# 2226051___ATmega128_Sheet.net
KiCad netlist of a schematic drawn in Altium Designer
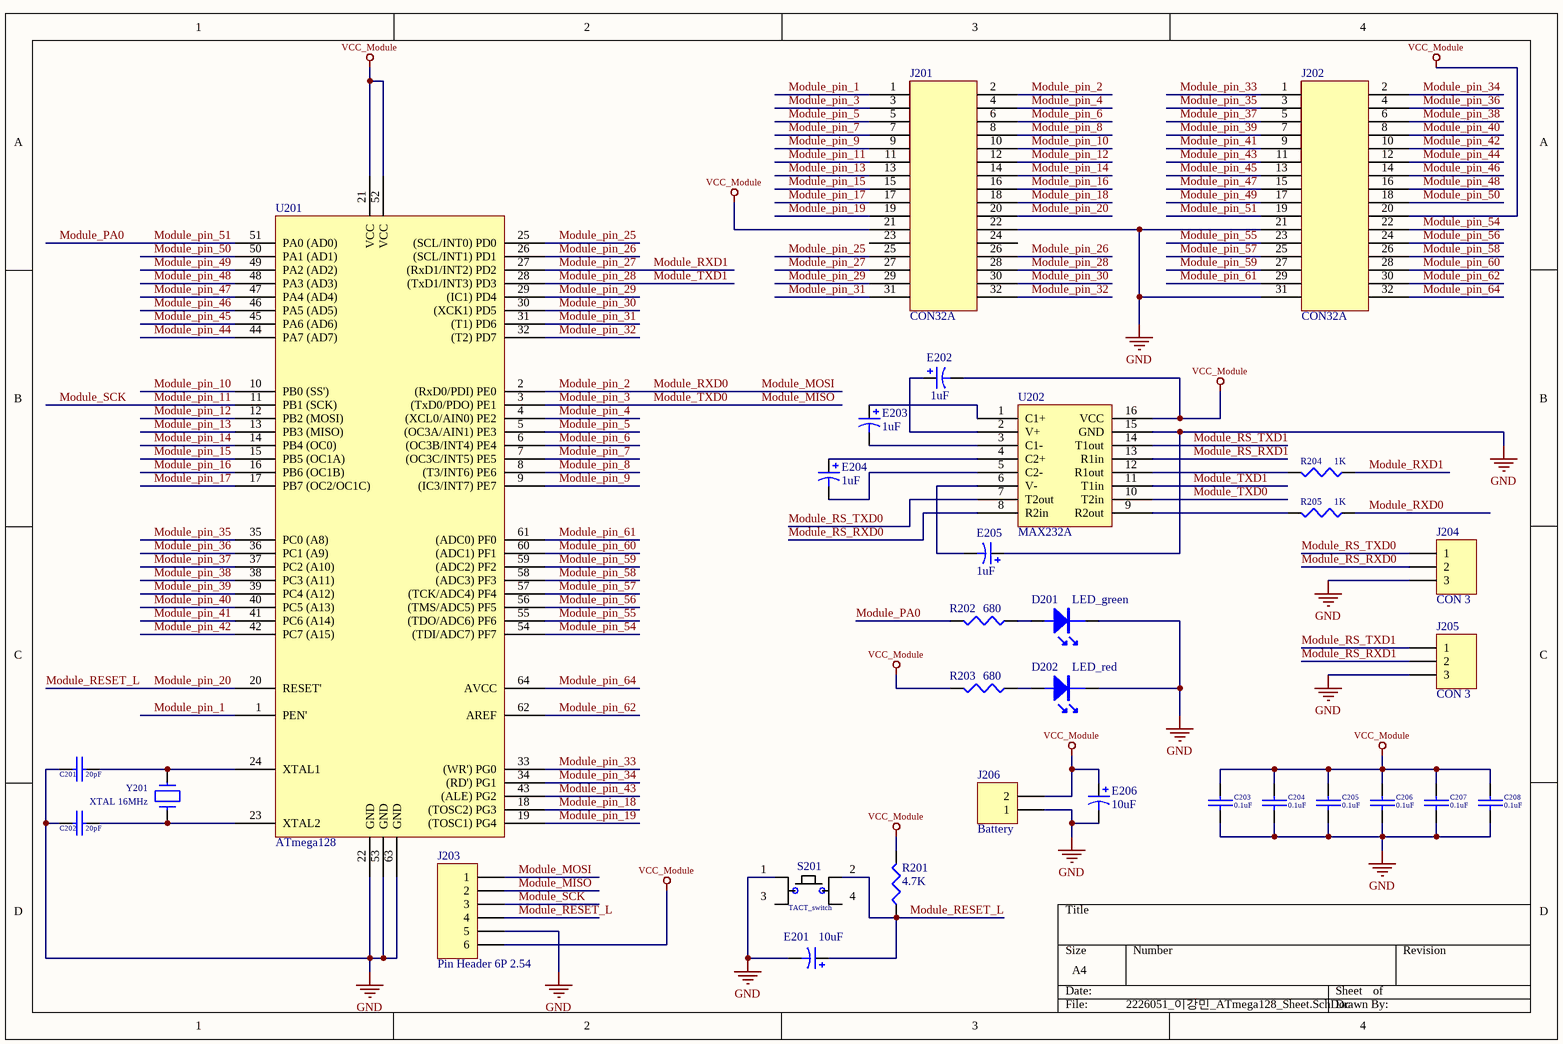
[diagram p0: 2226051_이강민_ATmega128_Sheet.SchDoc]

(export (version "E")
  (design (tool "Eeschema 10.0.6"))
  (components
    (comp (ref "C201")
      (value "20pF")
      (footprint "0603C1608")
      (description "SMDCapacitor")
      (libsource (lib "Miscellaneous Devices-KST") (part "CAP-Chip"))
    )
    (comp (ref "C202")
      (value "20pF")
      (footprint "0603C1608")
      (description "SMDCapacitor")
      (libsource (lib "Miscellaneous Devices-KST") (part "CAP-Chip"))
    )
    (comp (ref "C203")
      (value "0.1uF")
      (footprint "0603C1608")
      (description "SMDCapacitor")
      (libsource (lib "Miscellaneous Devices-KST") (part "CAP-Chip"))
    )
    (comp (ref "C204")
      (value "0.1uF")
      (footprint "0603C1608")
      (description "SMDCapacitor")
      (libsource (lib "Miscellaneous Devices-KST") (part "CAP-Chip"))
    )
    (comp (ref "C205")
      (value "0.1uF")
      (footprint "0603C1608")
      (description "SMDCapacitor")
      (libsource (lib "Miscellaneous Devices-KST") (part "CAP-Chip"))
    )
    (comp (ref "C206")
      (value "0.1uF")
      (footprint "0603C1608")
      (description "SMDCapacitor")
      (libsource (lib "Miscellaneous Devices-KST") (part "CAP-Chip"))
    )
    (comp (ref "C207")
      (value "0.1uF")
      (footprint "0603C1608")
      (description "SMDCapacitor")
      (libsource (lib "Miscellaneous Devices-KST") (part "CAP-Chip"))
    )
    (comp (ref "C208")
      (value "0.1uF")
      (footprint "0603C1608")
      (description "SMDCapacitor")
      (libsource (lib "Miscellaneous Devices-KST") (part "CAP-Chip"))
    )
    (comp (ref "D201")
      (value "LED_green")
      (footprint "LED-2012")
      (libsource (lib "Miscellaneous Devices-KST") (part "LED"))
    )
    (comp (ref "D202")
      (value "LED_red")
      (footprint "LED-2012")
      (libsource (lib "Miscellaneous Devices-KST") (part "LED"))
    )
    (comp (ref "E201")
      (value "10uF")
      (footprint "C0805")
      (description "Polarized Capacitor (Surface Mount)")
      (fields (field (name "Comment") "Cap Pol3") (field (name "PUBLISHER") "Altium Limited"))
      (libsource (lib "Miscellaneous Devices") (part "Cap Pol3"))
    )
    (comp (ref "E202")
      (value "1uF")
      (footprint "C0805")
      (description "Polarized Capacitor (Surface Mount)")
      (fields (field (name "Comment") "Cap Pol3") (field (name "PUBLISHER") "Altium Limited"))
      (libsource (lib "Miscellaneous Devices") (part "Cap Pol3"))
    )
    (comp (ref "E203")
      (value "1uF")
      (footprint "C0805")
      (description "Polarized Capacitor (Surface Mount)")
      (fields (field (name "Comment") "Cap Pol3") (field (name "PUBLISHER") "Altium Limited"))
      (libsource (lib "Miscellaneous Devices") (part "Cap Pol3"))
    )
    (comp (ref "E204")
      (value "1uF")
      (footprint "C0805")
      (description "Polarized Capacitor (Surface Mount)")
      (fields (field (name "Comment") "Cap Pol3") (field (name "PUBLISHER") "Altium Limited"))
      (libsource (lib "Miscellaneous Devices") (part "Cap Pol3"))
    )
    (comp (ref "E205")
      (value "1uF")
      (footprint "C0805")
      (description "Polarized Capacitor (Surface Mount)")
      (fields (field (name "Comment") "Cap Pol3") (field (name "PUBLISHER") "Altium Limited"))
      (libsource (lib "Miscellaneous Devices") (part "Cap Pol3"))
    )
    (comp (ref "E206")
      (value "10uF")
      (footprint "C0805")
      (description "Polarized Capacitor (Surface Mount)")
      (fields (field (name "Comment") "Cap Pol3") (field (name "PUBLISHER") "Altium Limited"))
      (libsource (lib "Miscellaneous Devices") (part "Cap Pol3"))
    )
    (comp (ref "J201")
      (value "CON32A")
      (footprint "CON32A")
      (libsource (lib "2226051_이강민_Schlib1") (part "CON32A"))
    )
    (comp (ref "J202")
      (value "CON32A")
      (footprint "CON32A")
      (libsource (lib "2226051_이강민_Schlib1") (part "CON32A"))
    )
    (comp (ref "J203")
      (value "Pin Header 6P 2.54")
      (footprint "ISP_connector")
      (description "Header, 6-Pin")
      (fields (field (name "PUBLISHER") "Altium Limited"))
      (libsource (lib "Miscellaneous Connectors") (part "Header 6"))
    )
    (comp (ref "J204")
      (value "CON 3")
      (footprint "RS-232_connector")
      (description "Header, 3-Pin")
      (fields (field (name "PUBLISHER") "Altium Limited"))
      (libsource (lib "Miscellaneous Connectors") (part "Header 3"))
    )
    (comp (ref "J205")
      (value "CON 3")
      (footprint "RS-232_connector")
      (description "Header, 3-Pin")
      (fields (field (name "PUBLISHER") "Altium Limited"))
      (libsource (lib "Miscellaneous Connectors") (part "Header 3"))
    )
    (comp (ref "J206")
      (value "Battery")
      (footprint "battery_2pin")
      (description "Header, 2-Pin")
      (fields (field (name "PUBLISHER") "Altium Limited"))
      (libsource (lib "Miscellaneous Connectors") (part "Header 2"))
    )
    (comp (ref "R201")
      (value "4.7K")
      (footprint "J1-0603")
      (description "Resistor")
      (fields (field (name "Comment") "Res3") (field (name "PUBLISHER") "Altium Limited"))
      (libsource (lib "Miscellaneous Devices") (part "Res3"))
    )
    (comp (ref "R202")
      (value "680")
      (footprint "J1-0603")
      (description "Resistor")
      (fields (field (name "Comment") "Res3") (field (name "PUBLISHER") "Altium Limited"))
      (libsource (lib "Miscellaneous Devices") (part "Res3"))
    )
    (comp (ref "R203")
      (value "680")
      (footprint "J1-0603")
      (description "Resistor")
      (fields (field (name "Comment") "Res3") (field (name "PUBLISHER") "Altium Limited"))
      (libsource (lib "Miscellaneous Devices") (part "Res3"))
    )
    (comp (ref "R204")
      (value "1K")
      (footprint "J1-0603")
      (description "Resistor")
      (fields (field (name "Comment") "Res3") (field (name "PUBLISHER") "Altium Limited"))
      (libsource (lib "Miscellaneous Devices") (part "Res3"))
    )
    (comp (ref "R205")
      (value "1K")
      (footprint "J1-0603")
      (description "Resistor")
      (fields (field (name "Comment") "Res3") (field (name "PUBLISHER") "Altium Limited"))
      (libsource (lib "Miscellaneous Devices") (part "Res3"))
    )
    (comp (ref "S201")
      (value "TACT_switch")
      (footprint "IT-1109S")
      (libsource (lib "2226051_이강민_Schlib1") (part "TACT_switch"))
    )
    (comp (ref "U201")
      (value "ATmega128")
      (footprint "ATmega128_1414")
      (libsource (lib "2226051_이강민_Schlib1") (part "ATmega128"))
    )
    (comp (ref "U202")
      (value "MAX232A")
      (footprint "MAX232A")
      (libsource (lib "2226051_이강민_Schlib1") (part "MAX232A"))
    )
    (comp (ref "Y201")
      (value "XTAL 16MHz")
      (footprint "X-TAL_SMD")
      (description "Crystal")
      (libsource (lib "Miscellaneous Devices-KST") (part "CRYSTAL"))
    )
  )
  (nets
    (net (code "1") (name "/Module_MISO") (class "Default")
      (node (ref "J201") (pin "3") (pintype "passive"))
      (node (ref "J203") (pin "2") (pinfunction "2_2") (pintype "passive"))
      (node (ref "U201") (pin "3") (pinfunction "(TxD0/PDO)_PE1_3") (pintype "passive"))
      (node (ref "U202") (pin "10") (pinfunction "T2in_10") (pintype "passive"))
    )
    (net (code "2") (name "/Module_MOSI") (class "Default")
      (node (ref "J201") (pin "2") (pintype "passive"))
      (node (ref "J203") (pin "1") (pinfunction "1_1") (pintype "passive"))
      (node (ref "R205") (pin "1") (pinfunction "1_1") (pintype "passive"))
      (node (ref "U201") (pin "2") (pinfunction "(RxD0/PDI)_PE0_2") (pintype "passive"))
    )
    (net (code "3") (name "/Module_PA0") (class "Default")
      (node (ref "J202") (pin "19") (pintype "passive"))
      (node (ref "R202") (pin "2") (pinfunction "2_2") (pintype "passive"))
      (node (ref "U201") (pin "51") (pinfunction "PA0_(AD0)_51") (pintype "passive"))
    )
    (net (code "4") (name "/Module_RESET_L") (class "Default")
      (node (ref "E201") (pin "1") (pinfunction "1_1") (pintype "passive"))
      (node (ref "J201") (pin "20") (pintype "passive"))
      (node (ref "J203") (pin "4") (pinfunction "4_4") (pintype "passive"))
      (node (ref "R201") (pin "1") (pinfunction "1_1") (pintype "passive"))
      (node (ref "S201") (pin "2") (pinfunction "2_2") (pintype "passive"))
      (node (ref "U201") (pin "20") (pinfunction "RESET'_20") (pintype "passive"))
    )
    (net (code "5") (name "/Module_RS_RXD0") (class "Default")
      (node (ref "J204") (pin "2") (pinfunction "2_2") (pintype "passive"))
      (node (ref "U202") (pin "8") (pinfunction "R2in_8") (pintype "passive"))
    )
    (net (code "6") (name "/Module_RS_RXD1") (class "Default")
      (node (ref "J205") (pin "2") (pinfunction "2_2") (pintype "passive"))
      (node (ref "U202") (pin "13") (pinfunction "R1in_13") (pintype "passive"))
    )
    (net (code "7") (name "/Module_RS_TXD0") (class "Default")
      (node (ref "J204") (pin "1") (pinfunction "1_1") (pintype "passive"))
      (node (ref "U202") (pin "7") (pinfunction "T2out_7") (pintype "passive"))
    )
    (net (code "8") (name "/Module_RS_TXD1") (class "Default")
      (node (ref "J205") (pin "1") (pinfunction "1_1") (pintype "passive"))
      (node (ref "U202") (pin "14") (pinfunction "T1out_14") (pintype "passive"))
    )
    (net (code "9") (name "/Module_RXD1") (class "Default")
      (node (ref "J201") (pin "27") (pintype "passive"))
      (node (ref "R204") (pin "1") (pinfunction "1_1") (pintype "passive"))
      (node (ref "U201") (pin "27") (pinfunction "(RxD1/INT2)_PD2_27") (pintype "passive"))
    )
    (net (code "10") (name "/Module_SCK") (class "Default")
      (node (ref "J201") (pin "11") (pintype "passive"))
      (node (ref "J203") (pin "3") (pinfunction "3_3") (pintype "passive"))
      (node (ref "U201") (pin "11") (pinfunction "PB1_(SCK)_11") (pintype "passive"))
    )
    (net (code "11") (name "/Module_TXD1") (class "Default")
      (node (ref "J201") (pin "28") (pintype "passive"))
      (node (ref "U201") (pin "28") (pinfunction "(TxD1/INT3)_PD3_28") (pintype "passive"))
      (node (ref "U202") (pin "11") (pinfunction "T1in_11") (pintype "passive"))
    )
    (net (code "12") (name "/Module_pin_1") (class "Default")
      (node (ref "J201") (pin "1") (pintype "passive"))
      (node (ref "U201") (pin "1") (pinfunction "PEN'_1") (pintype "passive"))
    )
    (net (code "13") (name "/Module_pin_4") (class "Default")
      (node (ref "J201") (pin "4") (pintype "passive"))
      (node (ref "U201") (pin "4") (pinfunction "(XCL0/AIN0)_PE2_4") (pintype "passive"))
    )
    (net (code "14") (name "/Module_pin_5") (class "Default")
      (node (ref "J201") (pin "5") (pintype "passive"))
      (node (ref "U201") (pin "5") (pinfunction "(OC3A/AIN1)_PE3_5") (pintype "passive"))
    )
    (net (code "15") (name "/Module_pin_6") (class "Default")
      (node (ref "J201") (pin "6") (pintype "passive"))
      (node (ref "U201") (pin "6") (pinfunction "(OC3B/INT4)_PE4_6") (pintype "passive"))
    )
    (net (code "16") (name "/Module_pin_7") (class "Default")
      (node (ref "J201") (pin "7") (pintype "passive"))
      (node (ref "U201") (pin "7") (pinfunction "(OC3C/INT5)_PE5_7") (pintype "passive"))
    )
    (net (code "17") (name "/Module_pin_8") (class "Default")
      (node (ref "J201") (pin "8") (pintype "passive"))
      (node (ref "U201") (pin "8") (pinfunction "(T3/INT6)_PE6_8") (pintype "passive"))
    )
    (net (code "18") (name "/Module_pin_9") (class "Default")
      (node (ref "J201") (pin "9") (pintype "passive"))
      (node (ref "U201") (pin "9") (pinfunction "(IC3/INT7)_PE7_9") (pintype "passive"))
    )
    (net (code "19") (name "/Module_pin_10") (class "Default")
      (node (ref "J201") (pin "10") (pintype "passive"))
      (node (ref "U201") (pin "10") (pinfunction "PB0_(SS')_10") (pintype "passive"))
    )
    (net (code "20") (name "/Module_pin_12") (class "Default")
      (node (ref "J201") (pin "12") (pintype "passive"))
      (node (ref "U201") (pin "12") (pinfunction "PB2_(MOSI)_12") (pintype "passive"))
    )
    (net (code "21") (name "/Module_pin_13") (class "Default")
      (node (ref "J201") (pin "13") (pintype "passive"))
      (node (ref "U201") (pin "13") (pinfunction "PB3_(MISO)_13") (pintype "passive"))
    )
    (net (code "22") (name "/Module_pin_14") (class "Default")
      (node (ref "J201") (pin "14") (pintype "passive"))
      (node (ref "U201") (pin "14") (pinfunction "PB4_(OC0)_14") (pintype "passive"))
    )
    (net (code "23") (name "/Module_pin_15") (class "Default")
      (node (ref "J201") (pin "15") (pintype "passive"))
      (node (ref "U201") (pin "15") (pinfunction "PB5_(OC1A)_15") (pintype "passive"))
    )
    (net (code "24") (name "/Module_pin_16") (class "Default")
      (node (ref "J201") (pin "16") (pintype "passive"))
      (node (ref "U201") (pin "16") (pinfunction "PB6_(OC1B)_16") (pintype "passive"))
    )
    (net (code "25") (name "/Module_pin_17") (class "Default")
      (node (ref "J201") (pin "17") (pintype "passive"))
      (node (ref "U201") (pin "17") (pinfunction "PB7_(OC2/OC1C)_17") (pintype "passive"))
    )
    (net (code "26") (name "/Module_pin_18") (class "Default")
      (node (ref "J201") (pin "18") (pintype "passive"))
      (node (ref "U201") (pin "18") (pinfunction "(TOSC2)_PG3_18") (pintype "passive"))
    )
    (net (code "27") (name "/Module_pin_19") (class "Default")
      (node (ref "J201") (pin "19") (pintype "passive"))
      (node (ref "U201") (pin "19") (pinfunction "(TOSC1)_PG4_19") (pintype "passive"))
    )
    (net (code "28") (name "/Module_pin_25") (class "Default")
      (node (ref "J201") (pin "25") (pintype "passive"))
      (node (ref "U201") (pin "25") (pinfunction "(SCL/INT0)_PD0_25") (pintype "passive"))
    )
    (net (code "29") (name "/Module_pin_26") (class "Default")
      (node (ref "J201") (pin "26") (pintype "passive"))
      (node (ref "U201") (pin "26") (pinfunction "(SCL/INT1)_PD1_26") (pintype "passive"))
    )
    (net (code "30") (name "/Module_pin_29") (class "Default")
      (node (ref "J201") (pin "29") (pintype "passive"))
      (node (ref "U201") (pin "29") (pinfunction "(IC1)_PD4_29") (pintype "passive"))
    )
    (net (code "31") (name "/Module_pin_30") (class "Default")
      (node (ref "J201") (pin "30") (pintype "passive"))
      (node (ref "U201") (pin "30") (pinfunction "(XCK1)_PD5_30") (pintype "passive"))
    )
    (net (code "32") (name "/Module_pin_31") (class "Default")
      (node (ref "J201") (pin "31") (pintype "passive"))
      (node (ref "U201") (pin "31") (pinfunction "(T1)_PD6_31") (pintype "passive"))
    )
    (net (code "33") (name "/Module_pin_32") (class "Default")
      (node (ref "J201") (pin "32") (pintype "passive"))
      (node (ref "U201") (pin "32") (pinfunction "(T2)_PD7_32") (pintype "passive"))
    )
    (net (code "34") (name "/Module_pin_33") (class "Default")
      (node (ref "J202") (pin "1") (pintype "passive"))
      (node (ref "U201") (pin "33") (pinfunction "(WR')_PG0_33") (pintype "passive"))
    )
    (net (code "35") (name "/Module_pin_34") (class "Default")
      (node (ref "J202") (pin "2") (pintype "passive"))
      (node (ref "U201") (pin "34") (pinfunction "(RD')_PG1_34") (pintype "passive"))
    )
    (net (code "36") (name "/Module_pin_35") (class "Default")
      (node (ref "J202") (pin "3") (pintype "passive"))
      (node (ref "U201") (pin "35") (pinfunction "PC0_(A8)_35") (pintype "passive"))
    )
    (net (code "37") (name "/Module_pin_36") (class "Default")
      (node (ref "J202") (pin "4") (pintype "passive"))
      (node (ref "U201") (pin "36") (pinfunction "PC1_(A9)_36") (pintype "passive"))
    )
    (net (code "38") (name "/Module_pin_37") (class "Default")
      (node (ref "J202") (pin "5") (pintype "passive"))
      (node (ref "U201") (pin "37") (pinfunction "PC2_(A10)_37") (pintype "passive"))
    )
    (net (code "39") (name "/Module_pin_38") (class "Default")
      (node (ref "J202") (pin "6") (pintype "passive"))
      (node (ref "U201") (pin "38") (pinfunction "PC3_(A11)_38") (pintype "passive"))
    )
    (net (code "40") (name "/Module_pin_39") (class "Default")
      (node (ref "J202") (pin "7") (pintype "passive"))
      (node (ref "U201") (pin "39") (pinfunction "PC4_(A12)_39") (pintype "passive"))
    )
    (net (code "41") (name "/Module_pin_40") (class "Default")
      (node (ref "J202") (pin "8") (pintype "passive"))
      (node (ref "U201") (pin "40") (pinfunction "PC5_(A13)_40") (pintype "passive"))
    )
    (net (code "42") (name "/Module_pin_41") (class "Default")
      (node (ref "J202") (pin "9") (pintype "passive"))
      (node (ref "U201") (pin "41") (pinfunction "PC6_(A14)_41") (pintype "passive"))
    )
    (net (code "43") (name "/Module_pin_42") (class "Default")
      (node (ref "J202") (pin "10") (pintype "passive"))
      (node (ref "U201") (pin "42") (pinfunction "PC7_(A15)_42") (pintype "passive"))
    )
    (net (code "44") (name "/Module_pin_43") (class "Default")
      (node (ref "J202") (pin "11") (pintype "passive"))
      (node (ref "U201") (pin "43") (pinfunction "(ALE)_PG2_43") (pintype "passive"))
    )
    (net (code "45") (name "/Module_pin_44") (class "Default")
      (node (ref "J202") (pin "12") (pintype "passive"))
      (node (ref "U201") (pin "44") (pinfunction "PA7_(AD7)_44") (pintype "passive"))
    )
    (net (code "46") (name "/Module_pin_45") (class "Default")
      (node (ref "J202") (pin "13") (pintype "passive"))
      (node (ref "U201") (pin "45") (pinfunction "PA6_(AD6)_45") (pintype "passive"))
    )
    (net (code "47") (name "/Module_pin_46") (class "Default")
      (node (ref "J202") (pin "14") (pintype "passive"))
      (node (ref "U201") (pin "46") (pinfunction "PA5_(AD5)_46") (pintype "passive"))
    )
    (net (code "48") (name "/Module_pin_47") (class "Default")
      (node (ref "J202") (pin "15") (pintype "passive"))
      (node (ref "U201") (pin "47") (pinfunction "PA4_(AD4)_47") (pintype "passive"))
    )
    (net (code "49") (name "/Module_pin_48") (class "Default")
      (node (ref "J202") (pin "16") (pintype "passive"))
      (node (ref "U201") (pin "48") (pinfunction "PA3_(AD3)_48") (pintype "passive"))
    )
    (net (code "50") (name "/Module_pin_49") (class "Default")
      (node (ref "J202") (pin "17") (pintype "passive"))
      (node (ref "U201") (pin "49") (pinfunction "PA2_(AD2)_49") (pintype "passive"))
    )
    (net (code "51") (name "/Module_pin_50") (class "Default")
      (node (ref "J202") (pin "18") (pintype "passive"))
      (node (ref "U201") (pin "50") (pinfunction "PA1_(AD1)_50") (pintype "passive"))
    )
    (net (code "52") (name "/Module_pin_54") (class "Default")
      (node (ref "J202") (pin "22") (pintype "passive"))
      (node (ref "U201") (pin "54") (pinfunction "(TDI/ADC7)_PF7_54") (pintype "passive"))
    )
    (net (code "53") (name "/Module_pin_55") (class "Default")
      (node (ref "J202") (pin "23") (pintype "passive"))
      (node (ref "U201") (pin "55") (pinfunction "(TDO/ADC6)_PF6_55") (pintype "passive"))
    )
    (net (code "54") (name "/Module_pin_56") (class "Default")
      (node (ref "J202") (pin "24") (pintype "passive"))
      (node (ref "U201") (pin "56") (pinfunction "(TMS/ADC5)_PF5_56") (pintype "passive"))
    )
    (net (code "55") (name "/Module_pin_57") (class "Default")
      (node (ref "J202") (pin "25") (pintype "passive"))
      (node (ref "U201") (pin "57") (pinfunction "(TCK/ADC4)_PF4_57") (pintype "passive"))
    )
    (net (code "56") (name "/Module_pin_58") (class "Default")
      (node (ref "J202") (pin "26") (pintype "passive"))
      (node (ref "U201") (pin "58") (pinfunction "(ADC3)_PF3_58") (pintype "passive"))
    )
    (net (code "57") (name "/Module_pin_59") (class "Default")
      (node (ref "J202") (pin "27") (pintype "passive"))
      (node (ref "U201") (pin "59") (pinfunction "(ADC2)_PF2_59") (pintype "passive"))
    )
    (net (code "58") (name "/Module_pin_60") (class "Default")
      (node (ref "J202") (pin "28") (pintype "passive"))
      (node (ref "U201") (pin "60") (pinfunction "(ADC1)_PF1_60") (pintype "passive"))
    )
    (net (code "59") (name "/Module_pin_61") (class "Default")
      (node (ref "J202") (pin "29") (pintype "passive"))
      (node (ref "U201") (pin "61") (pinfunction "(ADC0)_PF0_61") (pintype "passive"))
    )
    (net (code "60") (name "/Module_pin_62") (class "Default")
      (node (ref "J202") (pin "30") (pintype "passive"))
      (node (ref "U201") (pin "62") (pinfunction "AREF_62") (pintype "passive"))
    )
    (net (code "61") (name "/Module_pin_64") (class "Default")
      (node (ref "J202") (pin "32") (pintype "passive"))
      (node (ref "U201") (pin "64") (pinfunction "AVCC_64") (pintype "passive"))
    )
    (net (code "62") (name "GND") (class "Default")
      (node (ref "C201") (pin "1") (pinfunction "1_1") (pintype "passive"))
      (node (ref "C202") (pin "1") (pinfunction "1_1") (pintype "passive"))
      (node (ref "C203") (pin "1") (pinfunction "1_1") (pintype "passive"))
      (node (ref "C204") (pin "1") (pinfunction "1_1") (pintype "passive"))
      (node (ref "C205") (pin "1") (pinfunction "1_1") (pintype "passive"))
      (node (ref "C206") (pin "1") (pinfunction "1_1") (pintype "passive"))
      (node (ref "C207") (pin "1") (pinfunction "1_1") (pintype "passive"))
      (node (ref "C208") (pin "1") (pinfunction "1_1") (pintype "passive"))
      (node (ref "D201") (pin "2") (pinfunction "K_2") (pintype "passive"))
      (node (ref "D202") (pin "2") (pinfunction "K_2") (pintype "passive"))
      (node (ref "E201") (pin "2") (pinfunction "2_2") (pintype "passive"))
      (node (ref "E205") (pin "1") (pinfunction "1_1") (pintype "passive"))
      (node (ref "E206") (pin "2") (pinfunction "2_2") (pintype "passive"))
      (node (ref "J201") (pin "22") (pintype "passive"))
      (node (ref "J202") (pin "21") (pintype "passive"))
      (node (ref "J202") (pin "31") (pintype "passive"))
      (node (ref "J203") (pin "5") (pinfunction "5_5") (pintype "passive"))
      (node (ref "J204") (pin "3") (pinfunction "3_3") (pintype "passive"))
      (node (ref "J205") (pin "3") (pinfunction "3_3") (pintype "passive"))
      (node (ref "J206") (pin "1") (pinfunction "1_1") (pintype "passive"))
      (node (ref "S201") (pin "1") (pinfunction "1_1") (pintype "passive"))
      (node (ref "U201") (pin "22") (pinfunction "GND_22") (pintype "passive"))
      (node (ref "U201") (pin "53") (pinfunction "GND_53") (pintype "passive"))
      (node (ref "U201") (pin "63") (pinfunction "GND_63") (pintype "passive"))
      (node (ref "U202") (pin "15") (pinfunction "GND_15") (pintype "passive"))
    )
    (net (code "63") (name "Net-(D201-A)") (class "Default")
      (node (ref "D201") (pin "1") (pinfunction "A_1") (pintype "passive"))
      (node (ref "R202") (pin "1") (pinfunction "1_1") (pintype "passive"))
    )
    (net (code "64") (name "Net-(D202-A)") (class "Default")
      (node (ref "D202") (pin "1") (pinfunction "A_1") (pintype "passive"))
      (node (ref "R203") (pin "1") (pinfunction "1_1") (pintype "passive"))
    )
    (net (code "65") (name "Net-(U201-XTAL1)") (class "Default")
      (node (ref "C201") (pin "2") (pinfunction "2_2") (pintype "passive"))
      (node (ref "U201") (pin "24") (pinfunction "XTAL1_24") (pintype "passive"))
      (node (ref "Y201") (pin "2") (pinfunction "2_2") (pintype "passive"))
    )
    (net (code "66") (name "Net-(U201-XTAL2)") (class "Default")
      (node (ref "C202") (pin "2") (pinfunction "2_2") (pintype "passive"))
      (node (ref "U201") (pin "23") (pinfunction "XTAL2_23") (pintype "passive"))
      (node (ref "Y201") (pin "1") (pinfunction "1_1") (pintype "passive"))
    )
    (net (code "67") (name "Net-(U202-C1+)") (class "Default")
      (node (ref "E203") (pin "1") (pinfunction "1_1") (pintype "passive"))
      (node (ref "U202") (pin "1") (pinfunction "C1+_1") (pintype "passive"))
    )
    (net (code "68") (name "Net-(U202-C1-)") (class "Default")
      (node (ref "E203") (pin "2") (pinfunction "2_2") (pintype "passive"))
      (node (ref "U202") (pin "3") (pinfunction "C1-_3") (pintype "passive"))
    )
    (net (code "69") (name "Net-(U202-C2+)") (class "Default")
      (node (ref "E204") (pin "1") (pinfunction "1_1") (pintype "passive"))
      (node (ref "U202") (pin "4") (pinfunction "C2+_4") (pintype "passive"))
    )
    (net (code "70") (name "Net-(U202-C2-)") (class "Default")
      (node (ref "E204") (pin "2") (pinfunction "2_2") (pintype "passive"))
      (node (ref "U202") (pin "5") (pinfunction "C2-_5") (pintype "passive"))
    )
    (net (code "71") (name "Net-(U202-R1out)") (class "Default")
      (node (ref "R204") (pin "2") (pinfunction "2_2") (pintype "passive"))
      (node (ref "U202") (pin "12") (pinfunction "R1out_12") (pintype "passive"))
    )
    (net (code "72") (name "Net-(U202-R2out)") (class "Default")
      (node (ref "R205") (pin "2") (pinfunction "2_2") (pintype "passive"))
      (node (ref "U202") (pin "9") (pinfunction "R2out_9") (pintype "passive"))
    )
    (net (code "73") (name "Net-(U202-V+)") (class "Default")
      (node (ref "E202") (pin "1") (pinfunction "1_1") (pintype "passive"))
      (node (ref "U202") (pin "2") (pinfunction "V+_2") (pintype "passive"))
    )
    (net (code "74") (name "Net-(U202-V-)") (class "Default")
      (node (ref "E205") (pin "2") (pinfunction "2_2") (pintype "passive"))
      (node (ref "U202") (pin "6") (pinfunction "V-_6") (pintype "passive"))
    )
    (net (code "75") (name "VCC_Module") (class "Default")
      (node (ref "C203") (pin "2") (pinfunction "2_2") (pintype "passive"))
      (node (ref "C204") (pin "2") (pinfunction "2_2") (pintype "passive"))
      (node (ref "C205") (pin "2") (pinfunction "2_2") (pintype "passive"))
      (node (ref "C206") (pin "2") (pinfunction "2_2") (pintype "passive"))
      (node (ref "C207") (pin "2") (pinfunction "2_2") (pintype "passive"))
      (node (ref "C208") (pin "2") (pinfunction "2_2") (pintype "passive"))
      (node (ref "E202") (pin "2") (pinfunction "2_2") (pintype "passive"))
      (node (ref "E206") (pin "1") (pinfunction "1_1") (pintype "passive"))
      (node (ref "J201") (pin "21") (pintype "passive"))
      (node (ref "J202") (pin "20") (pintype "passive"))
      (node (ref "J203") (pin "6") (pinfunction "6_6") (pintype "passive"))
      (node (ref "J206") (pin "2") (pinfunction "2_2") (pintype "passive"))
      (node (ref "R201") (pin "2") (pinfunction "2_2") (pintype "passive"))
      (node (ref "R203") (pin "2") (pinfunction "2_2") (pintype "passive"))
      (node (ref "U201") (pin "21") (pinfunction "VCC_21") (pintype "passive"))
      (node (ref "U201") (pin "52") (pinfunction "VCC_52") (pintype "passive"))
      (node (ref "U202") (pin "16") (pinfunction "VCC_16") (pintype "passive"))
    )
    (net (code "76") (name "unconnected-(J201-Pad23)") (class "Default")
      (node (ref "J201") (pin "23") (pintype "passive"))
    )
    (net (code "77") (name "unconnected-(J201-Pad24)") (class "Default")
      (node (ref "J201") (pin "24") (pintype "passive"))
    )
    (net (code "78") (name "unconnected-(S201-Pad3)") (class "Default")
      (node (ref "S201") (pin "3") (pinfunction "3_3") (pintype "passive"))
    )
    (net (code "79") (name "unconnected-(S201-Pad4)") (class "Default")
      (node (ref "S201") (pin "4") (pinfunction "4_4") (pintype "passive"))
    )
  )
)
